# 16f628-final.net
KiCad netlist of a schematic drawn in EAGLE
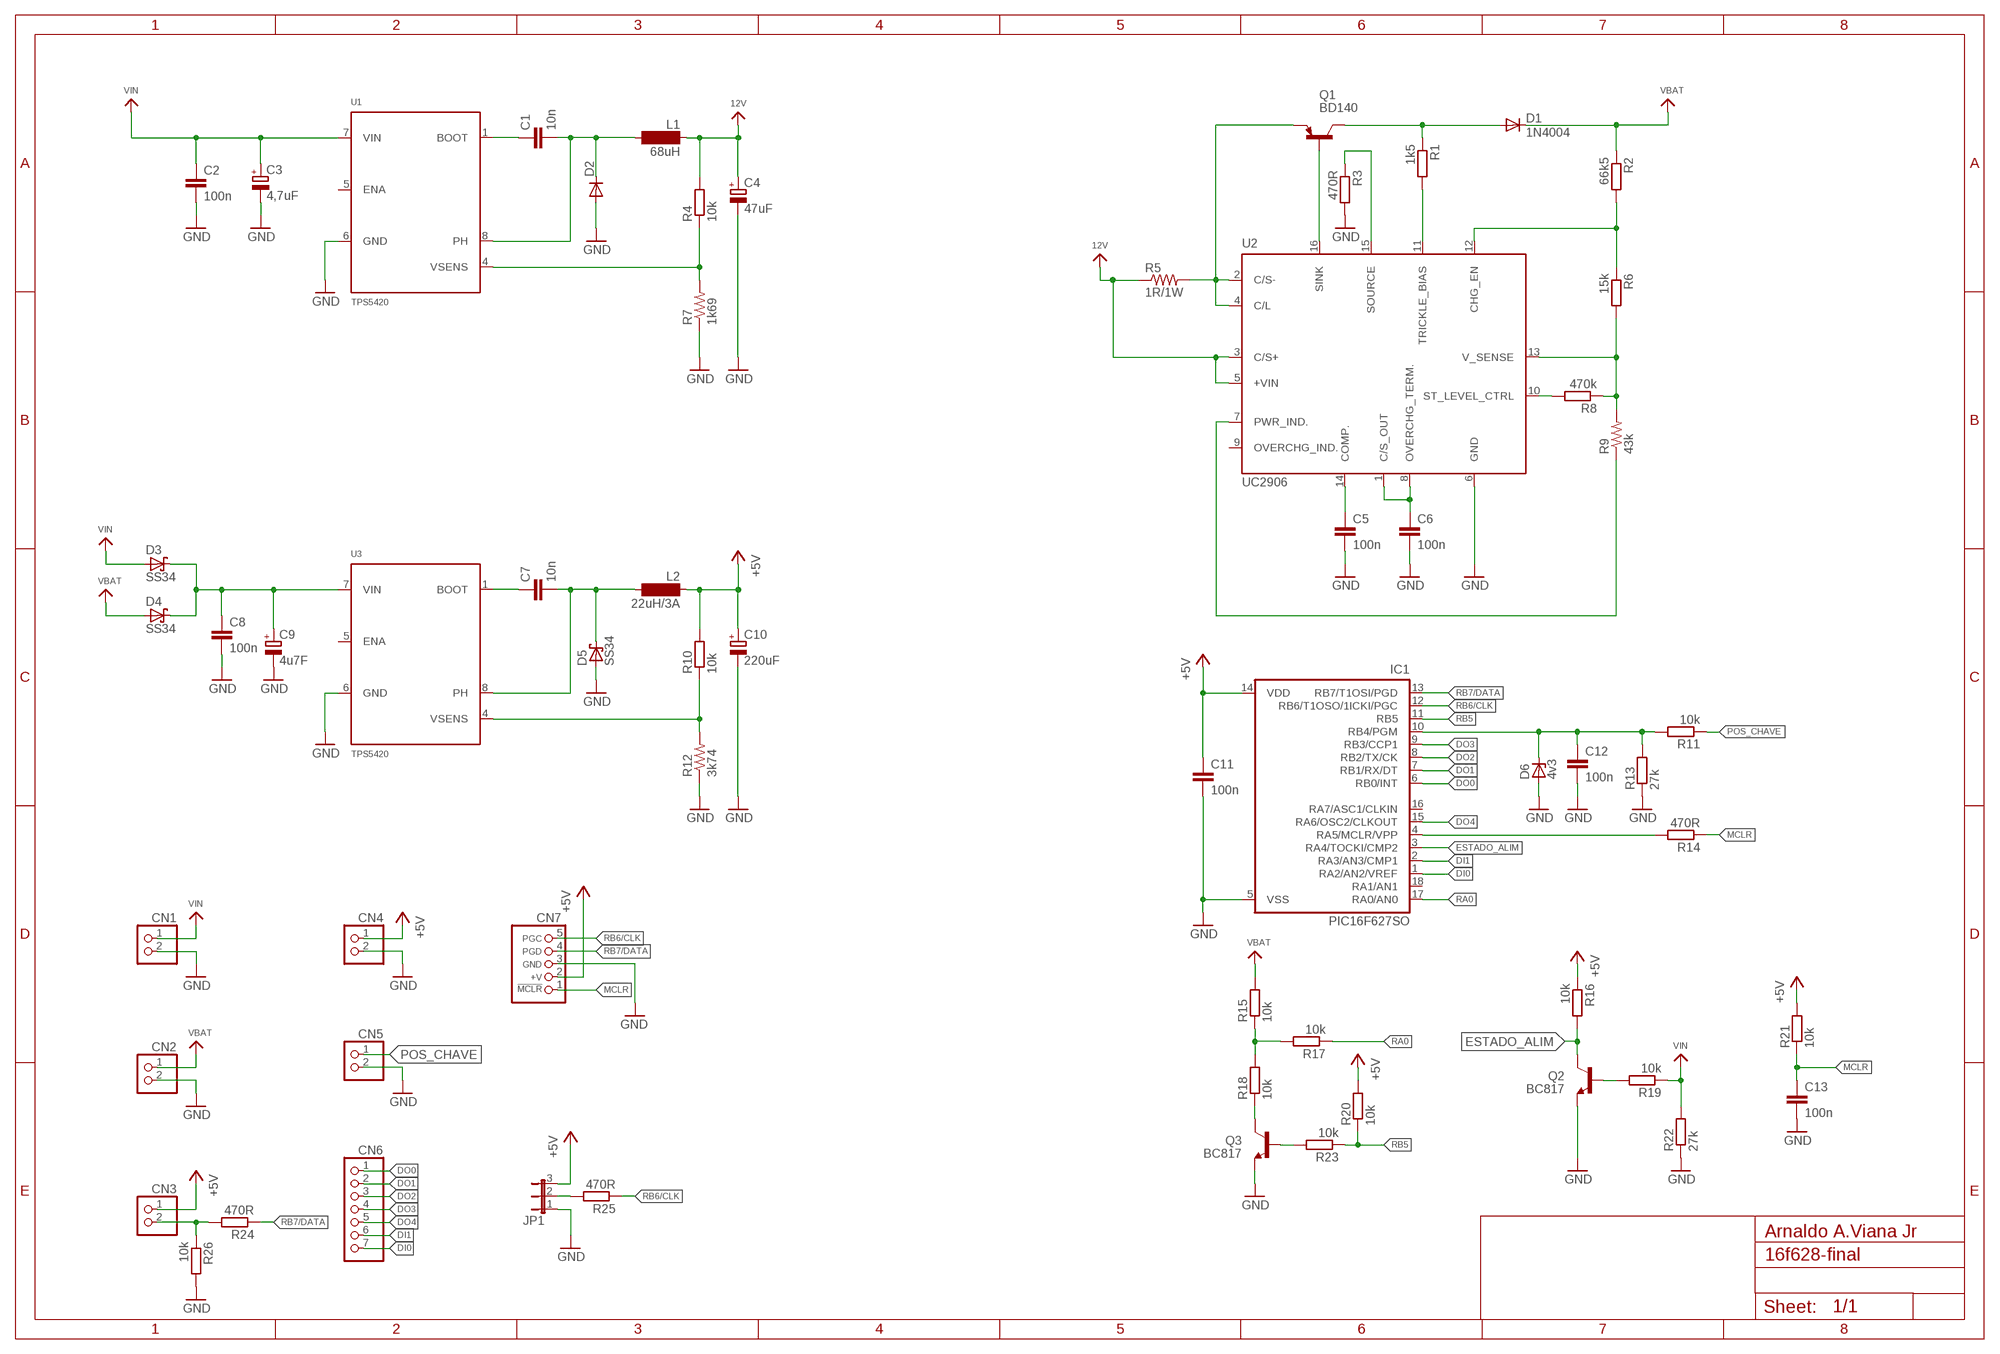
[diagram p0: schematic, sheet 1]

(export (version "E")
  (design (tool "Eeschema 10.0.6"))
  (components
    (comp (ref "C1")
      (value "10n")
      (footprint "eagle-import:C0805")
      (libsource (lib "eagle-import") (part "C-EUC0805"))
    )
    (comp (ref "C2")
      (value "100n")
      (footprint "eagle-import:C0805")
      (libsource (lib "eagle-import") (part "C-EUC0805"))
    )
    (comp (ref "C3")
      (value "4,7uF")
      (footprint "eagle-import:E2,5-6")
      (libsource (lib "eagle-import") (part "CPOL-EUE2.5-6"))
    )
    (comp (ref "C4")
      (value "47uF")
      (footprint "eagle-import:E2,5-6")
      (libsource (lib "eagle-import") (part "CPOL-EUE2.5-6"))
    )
    (comp (ref "C5")
      (value "100n")
      (footprint "eagle-import:C0805")
      (libsource (lib "eagle-import") (part "C-EUC0805"))
    )
    (comp (ref "C6")
      (value "100n")
      (footprint "eagle-import:C0805")
      (libsource (lib "eagle-import") (part "C-EUC0805"))
    )
    (comp (ref "C7")
      (value "10n")
      (footprint "eagle-import:C0805")
      (libsource (lib "eagle-import") (part "C-EUC0805"))
    )
    (comp (ref "C8")
      (value "100n")
      (footprint "eagle-import:C0805")
      (libsource (lib "eagle-import") (part "C-EUC0805"))
    )
    (comp (ref "C9")
      (value "4u7F")
      (footprint "eagle-import:E2,5-6")
      (libsource (lib "eagle-import") (part "CPOL-EUE2.5-6"))
    )
    (comp (ref "C10")
      (value "220uF")
      (footprint "eagle-import:E2,5-6")
      (libsource (lib "eagle-import") (part "CPOL-EUE2.5-6"))
    )
    (comp (ref "C11")
      (value "100n")
      (footprint "eagle-import:C0805")
      (libsource (lib "eagle-import") (part "C-EUC0805"))
    )
    (comp (ref "C12")
      (value "100n")
      (footprint "eagle-import:C0805")
      (libsource (lib "eagle-import") (part "C-EUC0805"))
    )
    (comp (ref "C13")
      (value "100n")
      (footprint "eagle-import:C0805")
      (libsource (lib "eagle-import") (part "C-EUC0805"))
    )
    (comp (ref "CN1")
      (value "HEADER-1X2ROUND")
      (footprint "eagle-import:1X02_ROUND")
      (libsource (lib "eagle-import") (part "HEADER-1X2ROUND"))
    )
    (comp (ref "CN2")
      (value "HEADER-1X2ROUND")
      (footprint "eagle-import:1X02_ROUND")
      (libsource (lib "eagle-import") (part "HEADER-1X2ROUND"))
    )
    (comp (ref "CN3")
      (value "HEADER-1X2ROUND")
      (footprint "eagle-import:1X02_ROUND")
      (libsource (lib "eagle-import") (part "HEADER-1X2ROUND"))
    )
    (comp (ref "CN4")
      (value "HEADER-1X2ROUND")
      (footprint "eagle-import:1X02_ROUND")
      (libsource (lib "eagle-import") (part "HEADER-1X2ROUND"))
    )
    (comp (ref "CN5")
      (value "HEADER-1X2ROUND")
      (footprint "eagle-import:1X02_ROUND")
      (libsource (lib "eagle-import") (part "HEADER-1X2ROUND"))
    )
    (comp (ref "CN6")
      (value "HEADER-1X7ROUND")
      (footprint "eagle-import:1X07_ROUND")
      (libsource (lib "eagle-import") (part "HEADER-1X7ROUND"))
    )
    (comp (ref "CN7")
      (value "CON_HEADER_PRG_PIC_ICSP0.1INCH_A")
      (footprint "eagle-import:HEADER_PRG_1X05")
      (libsource (lib "eagle-import") (part "CON_HEADER_PRG_PIC_ICSP0.1INCH_A"))
    )
    (comp (ref "D1")
      (value "1N4004")
      (footprint "eagle-import:DO41-10")
      (libsource (lib "eagle-import") (part "1N4004"))
    )
    (comp (ref "D2")
      (value "DIODE-SOD123")
      (footprint "eagle-import:SOD123")
      (libsource (lib "eagle-import") (part "DIODE-SOD123"))
    )
    (comp (ref "D3")
      (value "SS34")
      (footprint "eagle-import:SMC")
      (libsource (lib "eagle-import") (part "SCHOTTKY-DIODESMC"))
    )
    (comp (ref "D4")
      (value "SS34")
      (footprint "eagle-import:SMC")
      (libsource (lib "eagle-import") (part "SCHOTTKY-DIODESMC"))
    )
    (comp (ref "D5")
      (value "SS34")
      (footprint "eagle-import:SMC")
      (libsource (lib "eagle-import") (part "SCHOTTKY-DIODESMC"))
    )
    (comp (ref "D6")
      (value "4v3")
      (footprint "eagle-import:SOT23")
      (libsource (lib "eagle-import") (part "ZENER-DIODESOT23"))
    )
    (comp (ref "IC1")
      (value "PIC16F627SO")
      (footprint "eagle-import:SO-18W")
      (fields
        (field (name "MF") "MICROCHIP")
        (field (name "MPN") "PIC16F627-04/SO")
        (field (name "MPN_1") "PIC16F627-04/SO")
        (field (name "OC_FARNELL") "1084265")
        (field (name "OC_NEWARK") "69K7632")
      )
      (libsource (lib "eagle-import") (part "PIC16F627SO"))
    )
    (comp (ref "JP1")
      (value "JUMPER3")
      (footprint "eagle-import:JUMPER3")
      (libsource (lib "eagle-import") (part "JUMPER3"))
    )
    (comp (ref "L1")
      (value "68uH")
      (footprint "eagle-import:SD12K100")
      (libsource (lib "eagle-import") (part "SD12K100"))
    )
    (comp (ref "L2")
      (value "22uH/3A")
      (footprint "eagle-import:SD12K100")
      (libsource (lib "eagle-import") (part "SD12K100"))
    )
    (comp (ref "Q1")
      (value "BD140")
      (footprint "eagle-import:TO126")
      (libsource (lib "eagle-import") (part "BD140"))
    )
    (comp (ref "Q2")
      (value "BC817")
      (footprint "eagle-import:SOT23-BEC")
      (libsource (lib "eagle-import") (part "-NPN-SOT23-BECBC817-16"))
    )
    (comp (ref "Q3")
      (value "BC817")
      (footprint "eagle-import:SOT23-BEC")
      (libsource (lib "eagle-import") (part "-NPN-SOT23-BECBC817-16"))
    )
    (comp (ref "R1")
      (value "1k5")
      (footprint "eagle-import:R0805")
      (libsource (lib "eagle-import") (part "R-EU_R0805"))
    )
    (comp (ref "R2")
      (value "66k5")
      (footprint "eagle-import:R0805")
      (libsource (lib "eagle-import") (part "R-EU_R0805"))
    )
    (comp (ref "R3")
      (value "470R")
      (footprint "eagle-import:R0805")
      (libsource (lib "eagle-import") (part "R-EU_R0805"))
    )
    (comp (ref "R4")
      (value "10k")
      (footprint "eagle-import:R0805")
      (libsource (lib "eagle-import") (part "R-EU_R0805"))
    )
    (comp (ref "R5")
      (value "1R/1W")
      (footprint "eagle-import:0805-THM")
      (libsource (lib "eagle-import") (part "RESISTOR_DUAL"))
    )
    (comp (ref "R6")
      (value "15k")
      (footprint "eagle-import:R0805")
      (libsource (lib "eagle-import") (part "R-EU_R0805"))
    )
    (comp (ref "R7")
      (value "1k69")
      (footprint "eagle-import:0805-THM")
      (libsource (lib "eagle-import") (part "RESISTOR_DUAL"))
    )
    (comp (ref "R8")
      (value "470k")
      (footprint "eagle-import:R0805")
      (libsource (lib "eagle-import") (part "R-EU_R0805"))
    )
    (comp (ref "R9")
      (value "43k")
      (footprint "eagle-import:0805-THM")
      (libsource (lib "eagle-import") (part "RESISTOR_DUAL"))
    )
    (comp (ref "R10")
      (value "10k")
      (footprint "eagle-import:R0805")
      (libsource (lib "eagle-import") (part "R-EU_R0805"))
    )
    (comp (ref "R11")
      (value "10k")
      (footprint "eagle-import:R0805")
      (libsource (lib "eagle-import") (part "R-EU_R0805"))
    )
    (comp (ref "R12")
      (value "3k74")
      (footprint "eagle-import:0805-THM")
      (libsource (lib "eagle-import") (part "RESISTOR_DUAL"))
    )
    (comp (ref "R13")
      (value "27k")
      (footprint "eagle-import:R0805")
      (libsource (lib "eagle-import") (part "R-EU_R0805"))
    )
    (comp (ref "R14")
      (value "470R")
      (footprint "eagle-import:R0805")
      (libsource (lib "eagle-import") (part "R-EU_R0805"))
    )
    (comp (ref "R15")
      (value "10k")
      (footprint "eagle-import:R0805")
      (libsource (lib "eagle-import") (part "R-EU_R0805"))
    )
    (comp (ref "R16")
      (value "10k")
      (footprint "eagle-import:R0805")
      (libsource (lib "eagle-import") (part "R-EU_R0805"))
    )
    (comp (ref "R17")
      (value "10k")
      (footprint "eagle-import:R0805")
      (libsource (lib "eagle-import") (part "R-EU_R0805"))
    )
    (comp (ref "R18")
      (value "10k")
      (footprint "eagle-import:R0805")
      (libsource (lib "eagle-import") (part "R-EU_R0805"))
    )
    (comp (ref "R19")
      (value "10k")
      (footprint "eagle-import:R0805")
      (libsource (lib "eagle-import") (part "R-EU_R0805"))
    )
    (comp (ref "R20")
      (value "10k")
      (footprint "eagle-import:R0805")
      (libsource (lib "eagle-import") (part "R-EU_R0805"))
    )
    (comp (ref "R21")
      (value "10k")
      (footprint "eagle-import:R0805")
      (libsource (lib "eagle-import") (part "R-EU_R0805"))
    )
    (comp (ref "R22")
      (value "27k")
      (footprint "eagle-import:R0805")
      (libsource (lib "eagle-import") (part "R-EU_R0805"))
    )
    (comp (ref "R23")
      (value "10k")
      (footprint "eagle-import:R0805")
      (libsource (lib "eagle-import") (part "R-EU_R0805"))
    )
    (comp (ref "R24")
      (value "470R")
      (footprint "eagle-import:R0805")
      (libsource (lib "eagle-import") (part "R-EU_R0805"))
    )
    (comp (ref "R25")
      (value "470R")
      (footprint "eagle-import:R0805")
      (libsource (lib "eagle-import") (part "R-EU_R0805"))
    )
    (comp (ref "R26")
      (value "10k")
      (footprint "eagle-import:R0805")
      (libsource (lib "eagle-import") (part "R-EU_R0805"))
    )
    (comp (ref "U1")
      (value "TPS5420")
      (footprint "eagle-import:SOIC8_150MIL")
      (libsource (lib "eagle-import") (part "TPS5420"))
    )
    (comp (ref "U2")
      (value "UC2906")
      (footprint "eagle-import:SOIC_16")
      (libsource (lib "eagle-import") (part "UC2906"))
    )
    (comp (ref "U3")
      (value "TPS5420")
      (footprint "eagle-import:SOIC8_150MIL")
      (libsource (lib "eagle-import") (part "TPS5420"))
    )
  )
  (nets
    (net (code "1") (name "+5V") (class "Default")
      (node (ref "C10") (pin "+") (pinfunction "+_+") (pintype "passive"))
      (node (ref "C11") (pin "1") (pinfunction "1_1") (pintype "passive"))
      (node (ref "CN3") (pin "1") (pinfunction "1_1") (pintype "passive"))
      (node (ref "CN4") (pin "1") (pinfunction "1_1") (pintype "passive"))
      (node (ref "CN7") (pin "2") (pinfunction "+V_2") (pintype "passive"))
      (node (ref "IC1") (pin "14") (pinfunction "VDD_14") (pintype "power_in"))
      (node (ref "JP1") (pin "3") (pinfunction "3_3") (pintype "passive"))
      (node (ref "L2") (pin "1") (pinfunction "1_1") (pintype "passive"))
      (node (ref "R10") (pin "2") (pinfunction "2_2") (pintype "passive"))
      (node (ref "R16") (pin "1") (pinfunction "1_1") (pintype "passive"))
      (node (ref "R20") (pin "2") (pinfunction "2_2") (pintype "passive"))
      (node (ref "R21") (pin "2") (pinfunction "2_2") (pintype "passive"))
    )
    (net (code "2") (name "12V") (class "Default")
      (node (ref "C4") (pin "+") (pinfunction "+_+") (pintype "passive"))
      (node (ref "L1") (pin "1") (pinfunction "1_1") (pintype "passive"))
      (node (ref "R4") (pin "2") (pinfunction "2_2") (pintype "passive"))
      (node (ref "R5") (pin "1") (pinfunction "1_1") (pintype "passive"))
      (node (ref "U2") (pin "3") (pinfunction "C/S+_3") (pintype "bidirectional"))
      (node (ref "U2") (pin "5") (pinfunction "+VIN_5") (pintype "bidirectional"))
    )
    (net (code "3") (name "DI0") (class "Default")
      (node (ref "CN6") (pin "7") (pinfunction "7_7") (pintype "passive"))
      (node (ref "IC1") (pin "1") (pinfunction "RA2/AN2/VREF_1") (pintype "bidirectional"))
    )
    (net (code "4") (name "DI1") (class "Default")
      (node (ref "CN6") (pin "6") (pinfunction "6_6") (pintype "passive"))
      (node (ref "IC1") (pin "2") (pinfunction "RA3/AN3/CMP1_2") (pintype "bidirectional"))
    )
    (net (code "5") (name "DO0") (class "Default")
      (node (ref "CN6") (pin "1") (pinfunction "1_1") (pintype "passive"))
      (node (ref "IC1") (pin "6") (pinfunction "RB0/INT_6") (pintype "bidirectional"))
    )
    (net (code "6") (name "DO1") (class "Default")
      (node (ref "CN6") (pin "2") (pinfunction "2_2") (pintype "passive"))
      (node (ref "IC1") (pin "7") (pinfunction "RB1/RX/DT_7") (pintype "bidirectional"))
    )
    (net (code "7") (name "DO2") (class "Default")
      (node (ref "CN6") (pin "3") (pinfunction "3_3") (pintype "passive"))
      (node (ref "IC1") (pin "8") (pinfunction "RB2/TX/CK_8") (pintype "bidirectional"))
    )
    (net (code "8") (name "DO3") (class "Default")
      (node (ref "CN6") (pin "4") (pinfunction "4_4") (pintype "passive"))
      (node (ref "IC1") (pin "9") (pinfunction "RB3/CCP1_9") (pintype "bidirectional"))
    )
    (net (code "9") (name "DO4") (class "Default")
      (node (ref "CN6") (pin "5") (pinfunction "5_5") (pintype "passive"))
      (node (ref "IC1") (pin "15") (pinfunction "RA6/OSC2/CLKOUT_15") (pintype "bidirectional"))
    )
    (net (code "10") (name "ESTADO_ALIM") (class "Default")
      (node (ref "IC1") (pin "3") (pinfunction "RA4/TOCKI/CMP2_3") (pintype "bidirectional"))
      (node (ref "Q2") (pin "C") (pinfunction "C_C") (pintype "passive"))
      (node (ref "R16") (pin "2") (pinfunction "2_2") (pintype "passive"))
    )
    (net (code "11") (name "GND") (class "Default")
      (node (ref "C10") (pin "-") (pinfunction "-_-") (pintype "passive"))
      (node (ref "C11") (pin "2") (pinfunction "2_2") (pintype "passive"))
      (node (ref "C12") (pin "2") (pinfunction "2_2") (pintype "passive"))
      (node (ref "C13") (pin "2") (pinfunction "2_2") (pintype "passive"))
      (node (ref "C2") (pin "2") (pinfunction "2_2") (pintype "passive"))
      (node (ref "C3") (pin "-") (pinfunction "-_-") (pintype "passive"))
      (node (ref "C4") (pin "-") (pinfunction "-_-") (pintype "passive"))
      (node (ref "C5") (pin "2") (pinfunction "2_2") (pintype "passive"))
      (node (ref "C6") (pin "2") (pinfunction "2_2") (pintype "passive"))
      (node (ref "C8") (pin "2") (pinfunction "2_2") (pintype "passive"))
      (node (ref "C9") (pin "-") (pinfunction "-_-") (pintype "passive"))
      (node (ref "CN1") (pin "2") (pinfunction "2_2") (pintype "passive"))
      (node (ref "CN2") (pin "2") (pinfunction "2_2") (pintype "passive"))
      (node (ref "CN4") (pin "2") (pinfunction "2_2") (pintype "passive"))
      (node (ref "CN5") (pin "2") (pinfunction "2_2") (pintype "passive"))
      (node (ref "CN7") (pin "3") (pinfunction "GND_3") (pintype "passive"))
      (node (ref "D2") (pin "A") (pinfunction "A_A") (pintype "passive"))
      (node (ref "D5") (pin "A") (pinfunction "A_A") (pintype "passive"))
      (node (ref "D6") (pin "1") (pinfunction "A_1") (pintype "passive"))
      (node (ref "IC1") (pin "5") (pinfunction "VSS_5") (pintype "power_in"))
      (node (ref "JP1") (pin "1") (pinfunction "1_1") (pintype "passive"))
      (node (ref "Q2") (pin "E") (pinfunction "E_E") (pintype "passive"))
      (node (ref "Q3") (pin "E") (pinfunction "E_E") (pintype "passive"))
      (node (ref "R12") (pin "1") (pinfunction "1_1") (pintype "passive"))
      (node (ref "R13") (pin "1") (pinfunction "1_1") (pintype "passive"))
      (node (ref "R22") (pin "1") (pinfunction "1_1") (pintype "passive"))
      (node (ref "R26") (pin "2") (pinfunction "2_2") (pintype "passive"))
      (node (ref "R3") (pin "2") (pinfunction "2_2") (pintype "passive"))
      (node (ref "R7") (pin "1") (pinfunction "1_1") (pintype "passive"))
      (node (ref "U1") (pin "6") (pinfunction "GND_6") (pintype "bidirectional"))
      (node (ref "U2") (pin "6") (pinfunction "GND_6") (pintype "bidirectional"))
      (node (ref "U3") (pin "6") (pinfunction "GND_6") (pintype "bidirectional"))
    )
    (net (code "12") (name "MCLR") (class "Default")
      (node (ref "C13") (pin "1") (pinfunction "1_1") (pintype "passive"))
      (node (ref "CN7") (pin "1") (pinfunction "/MCLR_1") (pintype "passive"))
      (node (ref "R14") (pin "1") (pinfunction "1_1") (pintype "passive"))
      (node (ref "R21") (pin "1") (pinfunction "1_1") (pintype "passive"))
    )
    (net (code "13") (name "Net-(CN3-Pad2)") (class "Default")
      (node (ref "CN3") (pin "2") (pinfunction "2_2") (pintype "passive"))
      (node (ref "R24") (pin "2") (pinfunction "2_2") (pintype "passive"))
      (node (ref "R26") (pin "1") (pinfunction "1_1") (pintype "passive"))
    )
    (net (code "14") (name "Net-(D6-C)") (class "Default")
      (node (ref "C12") (pin "1") (pinfunction "1_1") (pintype "passive"))
      (node (ref "D6") (pin "3") (pinfunction "C_3") (pintype "passive"))
      (node (ref "IC1") (pin "10") (pinfunction "RB4/PGM_10") (pintype "bidirectional"))
      (node (ref "R11") (pin "2") (pinfunction "2_2") (pintype "passive"))
      (node (ref "R13") (pin "2") (pinfunction "2_2") (pintype "passive"))
    )
    (net (code "15") (name "Net-(IC1-RA5{slash}MCLR{slash}VPP)") (class "Default")
      (node (ref "IC1") (pin "4") (pinfunction "RA5/MCLR/VPP_4") (pintype "input"))
      (node (ref "R14") (pin "2") (pinfunction "2_2") (pintype "passive"))
    )
    (net (code "16") (name "Net-(JP1-Pad2)") (class "Default")
      (node (ref "JP1") (pin "2") (pinfunction "2_2") (pintype "passive"))
      (node (ref "R25") (pin "2") (pinfunction "2_2") (pintype "passive"))
    )
    (net (code "17") (name "Net-(Q1-B)") (class "Default")
      (node (ref "Q1") (pin "3") (pinfunction "B_3") (pintype "passive"))
      (node (ref "U2") (pin "16") (pinfunction "SINK_16") (pintype "bidirectional"))
    )
    (net (code "18") (name "Net-(Q1-C)") (class "Default")
      (node (ref "D1") (pin "A") (pinfunction "A_A") (pintype "passive"))
      (node (ref "Q1") (pin "2") (pinfunction "C_2") (pintype "passive"))
      (node (ref "R1") (pin "1") (pinfunction "1_1") (pintype "passive"))
    )
    (net (code "19") (name "Net-(Q1-E)") (class "Default")
      (node (ref "Q1") (pin "1") (pinfunction "E_1") (pintype "passive"))
      (node (ref "R5") (pin "2") (pinfunction "2_2") (pintype "passive"))
      (node (ref "U2") (pin "2") (pinfunction "C/S-_2") (pintype "bidirectional"))
      (node (ref "U2") (pin "4") (pinfunction "C/L_4") (pintype "bidirectional"))
    )
    (net (code "20") (name "Net-(Q2-PadB)") (class "Default")
      (node (ref "Q2") (pin "B") (pinfunction "B_B") (pintype "passive"))
      (node (ref "R19") (pin "2") (pinfunction "2_2") (pintype "passive"))
    )
    (net (code "21") (name "Net-(Q3-PadB)") (class "Default")
      (node (ref "Q3") (pin "B") (pinfunction "B_B") (pintype "passive"))
      (node (ref "R23") (pin "2") (pinfunction "2_2") (pintype "passive"))
    )
    (net (code "22") (name "Net-(Q3-PadC)") (class "Default")
      (node (ref "Q3") (pin "C") (pinfunction "C_C") (pintype "passive"))
      (node (ref "R18") (pin "1") (pinfunction "1_1") (pintype "passive"))
    )
    (net (code "23") (name "Net-(R15-Pad1)") (class "Default")
      (node (ref "R15") (pin "1") (pinfunction "1_1") (pintype "passive"))
      (node (ref "R17") (pin "2") (pinfunction "2_2") (pintype "passive"))
      (node (ref "R18") (pin "2") (pinfunction "2_2") (pintype "passive"))
    )
    (net (code "24") (name "Net-(U1-BOOT)") (class "Default")
      (node (ref "C1") (pin "1") (pinfunction "1_1") (pintype "passive"))
      (node (ref "U1") (pin "1") (pinfunction "BOOT_1") (pintype "bidirectional"))
    )
    (net (code "25") (name "Net-(U1-PH)") (class "Default")
      (node (ref "C1") (pin "2") (pinfunction "2_2") (pintype "passive"))
      (node (ref "D2") (pin "C") (pinfunction "C_C") (pintype "passive"))
      (node (ref "L1") (pin "2") (pinfunction "2_2") (pintype "passive"))
      (node (ref "U1") (pin "8") (pinfunction "PH_8") (pintype "bidirectional"))
    )
    (net (code "26") (name "Net-(U1-VSENS)") (class "Default")
      (node (ref "R4") (pin "1") (pinfunction "1_1") (pintype "passive"))
      (node (ref "R7") (pin "2") (pinfunction "2_2") (pintype "passive"))
      (node (ref "U1") (pin "4") (pinfunction "VSENS_4") (pintype "bidirectional"))
    )
    (net (code "27") (name "Net-(U2-CHG_EN)") (class "Default")
      (node (ref "R2") (pin "2") (pinfunction "2_2") (pintype "passive"))
      (node (ref "R6") (pin "1") (pinfunction "1_1") (pintype "passive"))
      (node (ref "U2") (pin "12") (pinfunction "CHG_EN_12") (pintype "bidirectional"))
    )
    (net (code "28") (name "Net-(U2-COMP.)") (class "Default")
      (node (ref "C5") (pin "1") (pinfunction "1_1") (pintype "passive"))
      (node (ref "U2") (pin "14") (pinfunction "COMP._14") (pintype "bidirectional"))
    )
    (net (code "29") (name "Net-(U2-C{slash}S_OUT)") (class "Default")
      (node (ref "C6") (pin "1") (pinfunction "1_1") (pintype "passive"))
      (node (ref "U2") (pin "1") (pinfunction "C/S_OUT_1") (pintype "bidirectional"))
      (node (ref "U2") (pin "8") (pinfunction "OVERCHG_TERM._8") (pintype "bidirectional"))
    )
    (net (code "30") (name "Net-(U2-PWR_IND.)") (class "Default")
      (node (ref "R9") (pin "1") (pinfunction "1_1") (pintype "passive"))
      (node (ref "U2") (pin "7") (pinfunction "PWR_IND._7") (pintype "bidirectional"))
    )
    (net (code "31") (name "Net-(U2-SOURCE)") (class "Default")
      (node (ref "R3") (pin "1") (pinfunction "1_1") (pintype "passive"))
      (node (ref "U2") (pin "15") (pinfunction "SOURCE_15") (pintype "bidirectional"))
    )
    (net (code "32") (name "Net-(U2-ST_LEVEL_CTRL)") (class "Default")
      (node (ref "R8") (pin "2") (pinfunction "2_2") (pintype "passive"))
      (node (ref "U2") (pin "10") (pinfunction "ST_LEVEL_CTRL_10") (pintype "bidirectional"))
    )
    (net (code "33") (name "Net-(U2-TRICKLE_BIAS)") (class "Default")
      (node (ref "R1") (pin "2") (pinfunction "2_2") (pintype "passive"))
      (node (ref "U2") (pin "11") (pinfunction "TRICKLE_BIAS_11") (pintype "bidirectional"))
    )
    (net (code "34") (name "Net-(U2-V_SENSE)") (class "Default")
      (node (ref "R6") (pin "2") (pinfunction "2_2") (pintype "passive"))
      (node (ref "R8") (pin "1") (pinfunction "1_1") (pintype "passive"))
      (node (ref "R9") (pin "2") (pinfunction "2_2") (pintype "passive"))
      (node (ref "U2") (pin "13") (pinfunction "V_SENSE_13") (pintype "bidirectional"))
    )
    (net (code "35") (name "Net-(U3-BOOT)") (class "Default")
      (node (ref "C7") (pin "1") (pinfunction "1_1") (pintype "passive"))
      (node (ref "U3") (pin "1") (pinfunction "BOOT_1") (pintype "bidirectional"))
    )
    (net (code "36") (name "Net-(U3-PH)") (class "Default")
      (node (ref "C7") (pin "2") (pinfunction "2_2") (pintype "passive"))
      (node (ref "D5") (pin "C") (pinfunction "C_C") (pintype "passive"))
      (node (ref "L2") (pin "2") (pinfunction "2_2") (pintype "passive"))
      (node (ref "U3") (pin "8") (pinfunction "PH_8") (pintype "bidirectional"))
    )
    (net (code "37") (name "Net-(U3-VIN)") (class "Default")
      (node (ref "C8") (pin "1") (pinfunction "1_1") (pintype "passive"))
      (node (ref "C9") (pin "+") (pinfunction "+_+") (pintype "passive"))
      (node (ref "D3") (pin "C") (pinfunction "C_C") (pintype "passive"))
      (node (ref "D4") (pin "C") (pinfunction "C_C") (pintype "passive"))
      (node (ref "U3") (pin "7") (pinfunction "VIN_7") (pintype "bidirectional"))
    )
    (net (code "38") (name "Net-(U3-VSENS)") (class "Default")
      (node (ref "R10") (pin "1") (pinfunction "1_1") (pintype "passive"))
      (node (ref "R12") (pin "2") (pinfunction "2_2") (pintype "passive"))
      (node (ref "U3") (pin "4") (pinfunction "VSENS_4") (pintype "bidirectional"))
    )
    (net (code "39") (name "POS_CHAVE") (class "Default")
      (node (ref "CN5") (pin "1") (pinfunction "1_1") (pintype "passive"))
      (node (ref "R11") (pin "1") (pinfunction "1_1") (pintype "passive"))
    )
    (net (code "40") (name "RA0") (class "Default")
      (node (ref "IC1") (pin "17") (pinfunction "RA0/AN0_17") (pintype "bidirectional"))
      (node (ref "R17") (pin "1") (pinfunction "1_1") (pintype "passive"))
    )
    (net (code "41") (name "RB5") (class "Default")
      (node (ref "IC1") (pin "11") (pinfunction "RB5_11") (pintype "bidirectional"))
      (node (ref "R20") (pin "1") (pinfunction "1_1") (pintype "passive"))
      (node (ref "R23") (pin "1") (pinfunction "1_1") (pintype "passive"))
    )
    (net (code "42") (name "RB6{slash}CLK") (class "Default")
      (node (ref "CN7") (pin "5") (pinfunction "PGC_5") (pintype "passive"))
      (node (ref "IC1") (pin "12") (pinfunction "RB6/T1OSO/1ICKI/PGC_12") (pintype "bidirectional"))
      (node (ref "R25") (pin "1") (pinfunction "1_1") (pintype "passive"))
    )
    (net (code "43") (name "RB7{slash}DATA") (class "Default")
      (node (ref "CN7") (pin "4") (pinfunction "PGD_4") (pintype "passive"))
      (node (ref "IC1") (pin "13") (pinfunction "RB7/T1OSI/PGD_13") (pintype "bidirectional"))
      (node (ref "R24") (pin "1") (pinfunction "1_1") (pintype "passive"))
    )
    (net (code "44") (name "VBAT") (class "Default")
      (node (ref "CN2") (pin "1") (pinfunction "1_1") (pintype "passive"))
      (node (ref "D1") (pin "C") (pinfunction "C_C") (pintype "passive"))
      (node (ref "D4") (pin "A") (pinfunction "A_A") (pintype "passive"))
      (node (ref "R15") (pin "2") (pinfunction "2_2") (pintype "passive"))
      (node (ref "R2") (pin "1") (pinfunction "1_1") (pintype "passive"))
    )
    (net (code "45") (name "VIN") (class "Default")
      (node (ref "C2") (pin "1") (pinfunction "1_1") (pintype "passive"))
      (node (ref "C3") (pin "+") (pinfunction "+_+") (pintype "passive"))
      (node (ref "CN1") (pin "1") (pinfunction "1_1") (pintype "passive"))
      (node (ref "D3") (pin "A") (pinfunction "A_A") (pintype "passive"))
      (node (ref "R19") (pin "1") (pinfunction "1_1") (pintype "passive"))
      (node (ref "R22") (pin "2") (pinfunction "2_2") (pintype "passive"))
      (node (ref "U1") (pin "7") (pinfunction "VIN_7") (pintype "bidirectional"))
    )
    (net (code "46") (name "unconnected-(IC1-RA1{slash}AN1-Pad18)") (class "Default")
      (node (ref "IC1") (pin "18") (pinfunction "RA1/AN1_18") (pintype "bidirectional"))
    )
    (net (code "47") (name "unconnected-(IC1-RA7{slash}ASC1{slash}CLKIN-Pad16)") (class "Default")
      (node (ref "IC1") (pin "16") (pinfunction "RA7/ASC1/CLKIN_16") (pintype "bidirectional"))
    )
    (net (code "48") (name "unconnected-(U1-ENA-Pad5)") (class "Default")
      (node (ref "U1") (pin "5") (pinfunction "ENA_5") (pintype "bidirectional"))
    )
    (net (code "49") (name "unconnected-(U2-OVERCHG_IND.-Pad9)") (class "Default")
      (node (ref "U2") (pin "9") (pinfunction "OVERCHG_IND._9") (pintype "bidirectional"))
    )
    (net (code "50") (name "unconnected-(U3-ENA-Pad5)") (class "Default")
      (node (ref "U3") (pin "5") (pinfunction "ENA_5") (pintype "bidirectional"))
    )
  )
)
